# STM32_Schematics.net
KiCad netlist of a schematic drawn in Altium Designer
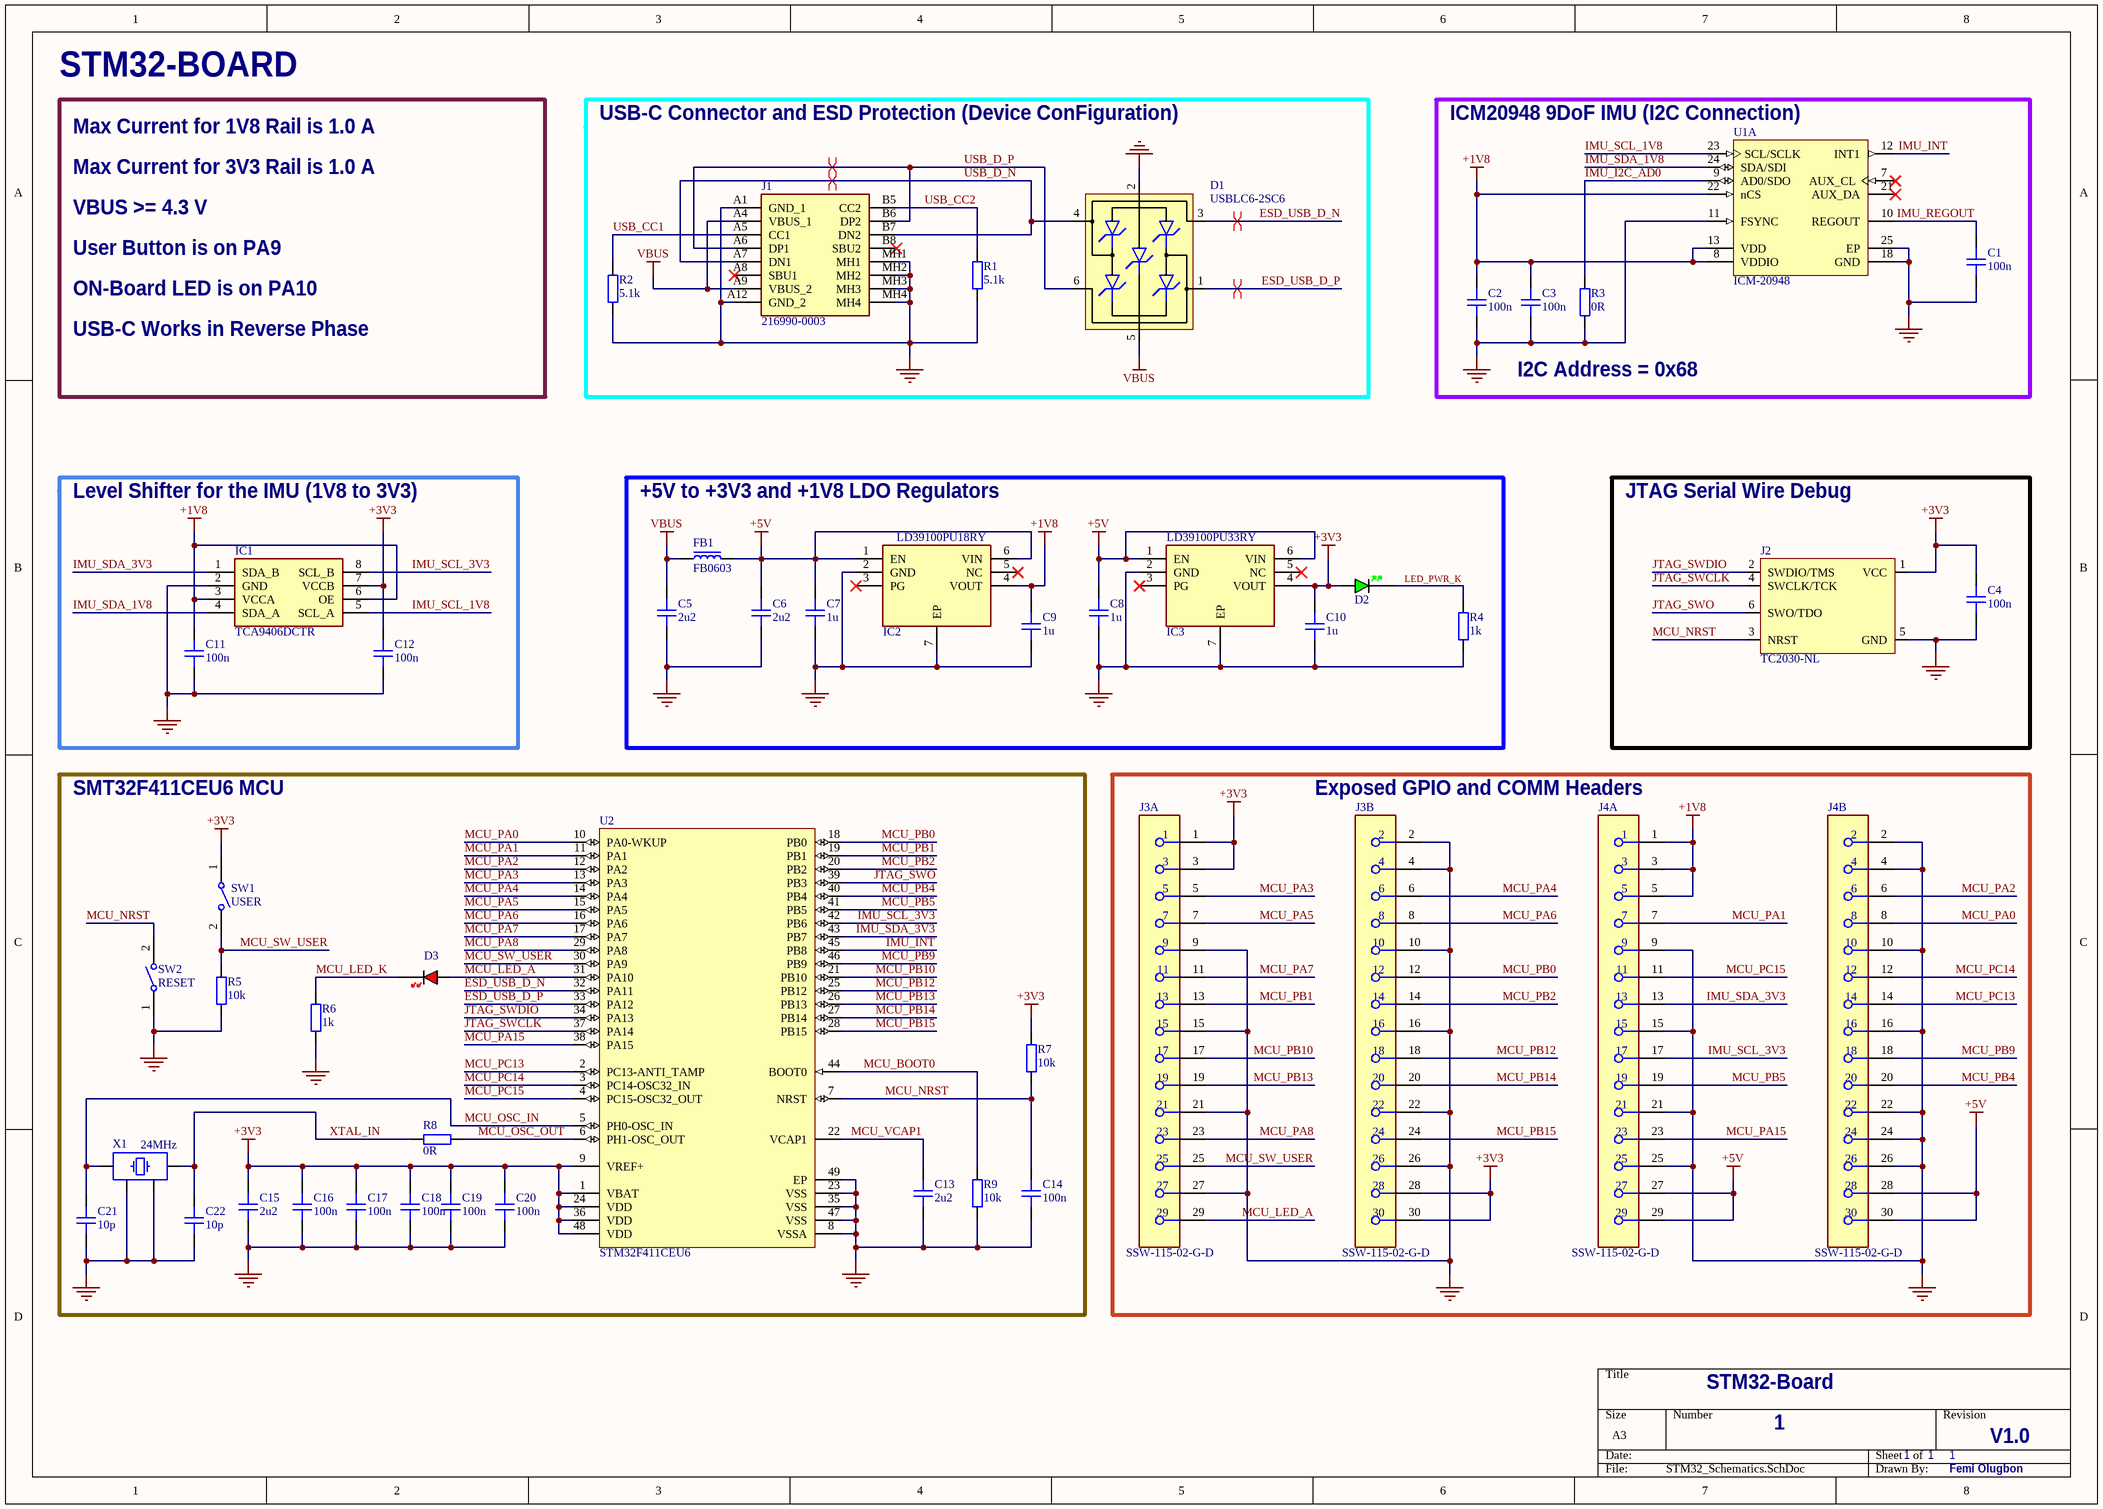
[diagram p0: STM32_Schematics.SchDoc]

(export (version "E")
  (design (tool "Eeschema 10.0.6"))
  (components
    (comp (ref "C1")
      (value "100n")
      (footprint "CAP_0402")
      (description "Capacitor SMD 0402")
      (libsource (lib "Schematic-Lib") (part "CAP_0402"))
    )
    (comp (ref "C2")
      (value "100n")
      (footprint "CAP_0402")
      (description "Capacitor SMD 0402")
      (libsource (lib "Schematic-Lib") (part "CAP_0402"))
    )
    (comp (ref "C3")
      (value "100n")
      (footprint "CAP_0402")
      (description "Capacitor SMD 0402")
      (libsource (lib "Schematic-Lib") (part "CAP_0402"))
    )
    (comp (ref "C4")
      (value "100n")
      (footprint "CAP_0402")
      (description "Capacitor SMD 0402")
      (libsource (lib "Schematic-Lib") (part "CAP_0402"))
    )
    (comp (ref "C5")
      (value "2u2")
      (footprint "CAP_0603")
      (description "Capacitor SMD 0603")
      (libsource (lib "Schematic-Lib") (part "CAP_0603"))
    )
    (comp (ref "C6")
      (value "2u2")
      (footprint "CAP_0603")
      (description "Capacitor SMD 0603")
      (libsource (lib "Schematic-Lib") (part "CAP_0603"))
    )
    (comp (ref "C7")
      (value "1u")
      (footprint "CAP_0603")
      (description "Capacitor SMD 0603")
      (libsource (lib "Schematic-Lib") (part "CAP_0603"))
    )
    (comp (ref "C8")
      (value "1u")
      (footprint "CAP_0603")
      (description "Capacitor SMD 0603")
      (libsource (lib "Schematic-Lib") (part "CAP_0603"))
    )
    (comp (ref "C9")
      (value "1u")
      (footprint "CAP_0603")
      (description "Capacitor SMD 0603")
      (libsource (lib "Schematic-Lib") (part "CAP_0603"))
    )
    (comp (ref "C10")
      (value "1u")
      (footprint "CAP_0603")
      (description "Capacitor SMD 0603")
      (libsource (lib "Schematic-Lib") (part "CAP_0603"))
    )
    (comp (ref "C11")
      (value "100n")
      (footprint "CAP_0402")
      (description "Capacitor SMD 0402")
      (libsource (lib "Schematic-Lib") (part "CAP_0402"))
    )
    (comp (ref "C12")
      (value "100n")
      (footprint "CAP_0402")
      (description "Capacitor SMD 0402")
      (libsource (lib "Schematic-Lib") (part "CAP_0402"))
    )
    (comp (ref "C13")
      (value "2u2")
      (footprint "CAP_0603")
      (description "Capacitor SMD 0603")
      (libsource (lib "Schematic-Lib") (part "CAP_0603"))
    )
    (comp (ref "C14")
      (value "100n")
      (footprint "CAP_0402")
      (description "Capacitor SMD 0402")
      (libsource (lib "Schematic-Lib") (part "CAP_0402"))
    )
    (comp (ref "C15")
      (value "2u2")
      (footprint "CAP_0603")
      (description "Capacitor SMD 0603")
      (libsource (lib "Schematic-Lib") (part "CAP_0603"))
    )
    (comp (ref "C16")
      (value "100n")
      (footprint "CAP_0402")
      (description "Capacitor SMD 0402")
      (libsource (lib "Schematic-Lib") (part "CAP_0402"))
    )
    (comp (ref "C17")
      (value "100n")
      (footprint "CAP_0402")
      (description "Capacitor SMD 0402")
      (libsource (lib "Schematic-Lib") (part "CAP_0402"))
    )
    (comp (ref "C18")
      (value "100n")
      (footprint "CAP_0402")
      (description "Capacitor SMD 0402")
      (libsource (lib "Schematic-Lib") (part "CAP_0402"))
    )
    (comp (ref "C19")
      (value "100n")
      (footprint "CAP_0402")
      (description "Capacitor SMD 0402")
      (libsource (lib "Schematic-Lib") (part "CAP_0402"))
    )
    (comp (ref "C20")
      (value "100n")
      (footprint "CAP_0402")
      (description "Capacitor SMD 0402")
      (libsource (lib "Schematic-Lib") (part "CAP_0402"))
    )
    (comp (ref "C21")
      (value "10p")
      (footprint "CAP_0402")
      (description "Capacitor SMD 0402")
      (libsource (lib "Schematic-Lib") (part "CAP_0402"))
    )
    (comp (ref "C22")
      (value "10p")
      (footprint "CAP_0402")
      (description "Capacitor SMD 0402")
      (libsource (lib "Schematic-Lib") (part "CAP_0402"))
    )
    (comp (ref "D1")
      (value "USBLC6-2SC6")
      (footprint "SOT-23-6")
      (description "Low-Capacitance ESD Protection USB")
      (fields (field (name "MANUFACTURER") "STMicroelectronics"))
      (libsource (lib "Schematic-Lib") (part "USBLC6-2SC6"))
    )
    (comp (ref "D2")
      (value "GREEN")
      (footprint "LED_0402_GREEN")
      (description "LED 0402 GREEN SMD")
      (libsource (lib "Schematic-Lib") (part "LED_0402_GREEN"))
    )
    (comp (ref "D3")
      (value "RED")
      (footprint "LED_0402_RED")
      (description "LED 0402 RED SMD")
      (libsource (lib "Schematic-Lib") (part "LED_0402_RED"))
    )
    (comp (ref "FB1")
      (value "FB0603")
      (footprint "FB_0603")
      (description "Ferrite Bead SMD 0603")
      (libsource (lib "Schematic-Lib") (part "FB_0603"))
    )
    (comp (ref "IC1")
      (value "TCA9406DCTR")
      (footprint "SamacSys:SOP65P400X130-8N")
      (description "Integrated Circuit")
      (fields (field (name "MOUSER PART NUMBER") "595-TCA9406DCTR"))
      (libsource (lib "*") (part "TCA9406DCTR"))
    )
    (comp (ref "IC2")
      (value "LD39100PU18RY")
      (footprint "SamacSys:SON95P300X300X90-7N-D")
      (description "Integrated Circuit")
      (fields (field (name "MOUSER PART NUMBER") "511-LD39100PU18RY"))
      (libsource (lib "Schematic-Lib") (part "LD39100PU18RY"))
    )
    (comp (ref "IC3")
      (value "LD39100PU33RY")
      (footprint "SamacSys:SON95P300X300X90-7N-D")
      (description "Integrated Circuit")
      (fields (field (name "MOUSER PART NUMBER") "511-LD39100PU33RY"))
      (libsource (lib "Schematic-Lib") (part "LD39100PU33RY"))
    )
    (comp (ref "J1")
      (value "216990-0003")
      (footprint "2169900003")
      (description "Connector")
      (fields (field (name "MOUSER PART NUMBER") "538-216990-0003"))
      (libsource (lib "Schematic-Lib") (part "216990-0003"))
    )
    (comp (ref "J2")
      (value "TC2030-NL")
      (footprint "TC2030-NL-FP")
      (description "Tag-Connect No-Solder SWD Debug Connector (No Legs) DO NOT PLACE")
      (fields
        (field (name "MANUFACTURER") "Tag-Connect")
        (field (name "MANUFACTURER PART NUMBER") "TC2030-NL-FP")
      )
      (libsource (lib "Schematic-Lib") (part "TC2030-NL"))
    )
    (comp (ref "J3")
      (value "SSW-115-02-G-D")
      (footprint "FP-SSW-115-02-G-D-MFG")
      (description "SSW-115-02-G-D SSW - Samtec 2.54mm Dual Row Straight Socket Strip 8.5mm Profile (mcv)(TO22)")
      (libsource (lib "Altium Content Vault") (part "58658856964e77fd1e9d81751433862"))
    )
    (comp (ref "J4")
      (value "SSW-115-02-G-D")
      (footprint "FP-SSW-115-02-G-D-MFG")
      (description "SSW-115-02-G-D SSW - Samtec 2.54mm Dual Row Straight Socket Strip 8.5mm Profile (mcv)(TO22)")
      (libsource (lib "Altium Content Vault") (part "58658856964e77fd1e9d81751433862"))
    )
    (comp (ref "R1")
      (value "5.1k")
      (footprint "RES_0402")
      (description "Resistor SMD 0402")
      (libsource (lib "Schematic-Lib") (part "RES_0402"))
    )
    (comp (ref "R2")
      (value "5.1k")
      (footprint "RES_0402")
      (description "Resistor SMD 0402")
      (libsource (lib "Schematic-Lib") (part "RES_0402"))
    )
    (comp (ref "R3")
      (value "0R")
      (footprint "RES_0402")
      (description "Resistor SMD 0402")
      (libsource (lib "Schematic-Lib") (part "RES_0402"))
    )
    (comp (ref "R4")
      (value "1k")
      (footprint "RES_0402")
      (description "Resistor SMD 0402")
      (libsource (lib "Schematic-Lib") (part "RES_0402"))
    )
    (comp (ref "R5")
      (value "10k")
      (footprint "RES_0402")
      (description "Resistor SMD 0402")
      (libsource (lib "Schematic-Lib") (part "RES_0402"))
    )
    (comp (ref "R6")
      (value "1k")
      (footprint "RES_0402")
      (description "Resistor SMD 0402")
      (libsource (lib "Schematic-Lib") (part "RES_0402"))
    )
    (comp (ref "R7")
      (value "10k")
      (footprint "RES_0402")
      (description "Resistor SMD 0402")
      (libsource (lib "Schematic-Lib") (part "RES_0402"))
    )
    (comp (ref "R8")
      (value "0R")
      (footprint "RES_0402")
      (description "Resistor SMD 0402")
      (libsource (lib "Schematic-Lib") (part "RES_0402"))
    )
    (comp (ref "R9")
      (value "10k")
      (footprint "RES_0402")
      (description "Resistor SMD 0402")
      (libsource (lib "Schematic-Lib") (part "RES_0402"))
    )
    (comp (ref "SW1")
      (value "USER")
      (footprint "TECO-FSMSM-2_V")
      (description "FSMSM Push Button Switch, 50 mA, -35 to 85 degC, 2-Pin SMD, RoHS, Bulk")
      (fields (field (name "MANUFACTURER") "TE Connectivity"))
      (libsource (lib "Altium Content Vault") (part "SW-SPST-2_C"))
    )
    (comp (ref "SW2")
      (value "RESET")
      (footprint "TECO-FSMSM-2_V")
      (description "FSMSM Push Button Switch, 50 mA, -35 to 85 degC, 2-Pin SMD, RoHS, Bulk")
      (fields (field (name "MANUFACTURER") "TE Connectivity"))
      (libsource (lib "Altium Content Vault") (part "SW-SPST-2_C"))
    )
    (comp (ref "U1")
      (value "ICM-20948")
      (footprint "TDK-QFN-24_L")
      (fields (field (name "MANUFACTURER") "TDK"))
      (libsource (lib "Altium Content Vault") (part "TDK-ICM-20948-QFN-24"))
    )
    (comp (ref "U2")
      (value "STM32F411CEU6")
      (footprint "STM-UFQFPN48_L")
      (libsource (lib "Altium Content Vault") (part "MC-ARM-STM32F411-UFQFPN48"))
    )
    (comp (ref "X1")
      (value "24MHz")
      (footprint "XTAL_3225")
      (description "Crystal SMD 24MHz 10PPM 7pF 3225")
      (fields
        (field (name "MANUFACTURER") "Epson")
        (field (name "MANUFACTURER PART NUMBER") "TSX-3225 24.0000MF15X-AC")
      )
      (libsource (lib "Schematic-Lib") (part "TSX-3225_24.0000MF15X-AC"))
    )
  )
  (nets
    (net (code "1") (name "+1V8") (class "Default")
      (node (ref "C11") (pin "1") (pinfunction "1_1") (pintype "passive"))
      (node (ref "C2") (pin "1") (pinfunction "1_1") (pintype "passive"))
      (node (ref "C3") (pin "1") (pinfunction "1_1") (pintype "passive"))
      (node (ref "C9") (pin "2") (pinfunction "2_2") (pintype "passive"))
      (node (ref "IC1") (pin "3") (pinfunction "VCCA_3") (pintype "passive"))
      (node (ref "IC1") (pin "6") (pinfunction "OE_6") (pintype "passive"))
      (node (ref "IC2") (pin "4") (pinfunction "VOUT_4") (pintype "passive"))
      (node (ref "J4") (pin "1") (pinfunction "1_1") (pintype "passive"))
      (node (ref "J4") (pin "3") (pinfunction "3_3") (pintype "passive"))
      (node (ref "J4") (pin "5") (pinfunction "5_5") (pintype "passive"))
      (node (ref "U1") (pin "13") (pinfunction "VDD_13") (pintype "power_in"))
      (node (ref "U1") (pin "22") (pinfunction "nCS_22") (pintype "input"))
      (node (ref "U1") (pin "8") (pinfunction "VDDIO_8") (pintype "power_in"))
    )
    (net (code "2") (name "+3V3") (class "Default")
      (node (ref "C10") (pin "2") (pinfunction "2_2") (pintype "passive"))
      (node (ref "C12") (pin "1") (pinfunction "1_1") (pintype "passive"))
      (node (ref "C15") (pin "2") (pinfunction "2_2") (pintype "passive"))
      (node (ref "C16") (pin "1") (pinfunction "1_1") (pintype "passive"))
      (node (ref "C17") (pin "1") (pinfunction "1_1") (pintype "passive"))
      (node (ref "C18") (pin "1") (pinfunction "1_1") (pintype "passive"))
      (node (ref "C19") (pin "1") (pinfunction "1_1") (pintype "passive"))
      (node (ref "C20") (pin "1") (pinfunction "1_1") (pintype "passive"))
      (node (ref "C4") (pin "1") (pinfunction "1_1") (pintype "passive"))
      (node (ref "D2") (pin "A") (pinfunction "A_A") (pintype "passive"))
      (node (ref "IC1") (pin "7") (pinfunction "VCCB_7") (pintype "passive"))
      (node (ref "IC3") (pin "4") (pinfunction "VOUT_4") (pintype "passive"))
      (node (ref "J2") (pin "1") (pinfunction "VCC_1") (pintype "passive"))
      (node (ref "J3") (pin "1") (pinfunction "1_1") (pintype "passive"))
      (node (ref "J3") (pin "28") (pinfunction "28_28") (pintype "passive"))
      (node (ref "J3") (pin "3") (pinfunction "3_3") (pintype "passive"))
      (node (ref "J3") (pin "30") (pinfunction "30_30") (pintype "passive"))
      (node (ref "R7") (pin "2") (pinfunction "2_2") (pintype "passive"))
      (node (ref "SW1") (pin "1") (pinfunction "1_1") (pintype "passive"))
      (node (ref "U2") (pin "1") (pinfunction "VBAT_1") (pintype "power_in"))
      (node (ref "U2") (pin "24") (pinfunction "VDD_24") (pintype "power_in"))
      (node (ref "U2") (pin "36") (pinfunction "VDD_36") (pintype "power_in"))
      (node (ref "U2") (pin "48") (pinfunction "VDD_48") (pintype "power_in"))
      (node (ref "U2") (pin "9") (pinfunction "VREF+_9") (pintype "power_in"))
    )
    (net (code "3") (name "+5V") (class "Default")
      (node (ref "C6") (pin "2") (pinfunction "2_2") (pintype "passive"))
      (node (ref "C7") (pin "2") (pinfunction "2_2") (pintype "passive"))
      (node (ref "C8") (pin "2") (pinfunction "2_2") (pintype "passive"))
      (node (ref "FB1") (pin "2") (pinfunction "2_2") (pintype "passive"))
      (node (ref "IC2") (pin "1") (pinfunction "EN_1") (pintype "passive"))
      (node (ref "IC2") (pin "6") (pinfunction "VIN_6") (pintype "passive"))
      (node (ref "IC3") (pin "1") (pinfunction "EN_1") (pintype "passive"))
      (node (ref "IC3") (pin "6") (pinfunction "VIN_6") (pintype "passive"))
      (node (ref "J4") (pin "27") (pinfunction "27_27") (pintype "passive"))
      (node (ref "J4") (pin "28") (pinfunction "28_28") (pintype "passive"))
      (node (ref "J4") (pin "29") (pinfunction "29_29") (pintype "passive"))
      (node (ref "J4") (pin "30") (pinfunction "30_30") (pintype "passive"))
    )
    (net (code "4") (name "/ESD_USB_D_N") (class "Default")
      (node (ref "D1") (pin "3") (pinfunction "IO2_3") (pintype "bidirectional"))
      (node (ref "U2") (pin "32") (pinfunction "PA11_32") (pintype "bidirectional"))
    )
    (net (code "5") (name "/ESD_USB_D_P") (class "Default")
      (node (ref "D1") (pin "1") (pinfunction "IO1_1") (pintype "bidirectional"))
      (node (ref "U2") (pin "33") (pinfunction "PA12_33") (pintype "bidirectional"))
    )
    (net (code "6") (name "/IMU_I2C_AD0") (class "Default")
      (node (ref "R3") (pin "2") (pinfunction "2_2") (pintype "passive"))
      (node (ref "U1") (pin "9") (pinfunction "AD0/SDO_9") (pintype "bidirectional"))
    )
    (net (code "7") (name "/IMU_INT") (class "Default")
      (node (ref "U1") (pin "12") (pinfunction "INT1_12") (pintype "output"))
      (node (ref "U2") (pin "45") (pinfunction "PB8_45") (pintype "bidirectional"))
    )
    (net (code "8") (name "/IMU_REGOUT") (class "Default")
      (node (ref "C1") (pin "1") (pinfunction "1_1") (pintype "passive"))
      (node (ref "U1") (pin "10") (pinfunction "REGOUT_10") (pintype "passive"))
    )
    (net (code "9") (name "/IMU_SCL_1V8") (class "Default")
      (node (ref "IC1") (pin "5") (pinfunction "SCL_A_5") (pintype "passive"))
      (node (ref "U1") (pin "23") (pinfunction "SCL/SCLK_23") (pintype "input"))
    )
    (net (code "10") (name "/IMU_SCL_3V3") (class "Default")
      (node (ref "IC1") (pin "8") (pinfunction "SCL_B_8") (pintype "passive"))
      (node (ref "J4") (pin "17") (pinfunction "17_17") (pintype "passive"))
      (node (ref "U2") (pin "42") (pinfunction "PB6_42") (pintype "bidirectional"))
    )
    (net (code "11") (name "/IMU_SDA_1V8") (class "Default")
      (node (ref "IC1") (pin "4") (pinfunction "SDA_A_4") (pintype "passive"))
      (node (ref "U1") (pin "24") (pinfunction "SDA/SDI_24") (pintype "bidirectional"))
    )
    (net (code "12") (name "/IMU_SDA_3V3") (class "Default")
      (node (ref "IC1") (pin "1") (pinfunction "SDA_B_1") (pintype "passive"))
      (node (ref "J4") (pin "13") (pinfunction "13_13") (pintype "passive"))
      (node (ref "U2") (pin "43") (pinfunction "PB7_43") (pintype "bidirectional"))
    )
    (net (code "13") (name "/JTAG_SWCLK") (class "Default")
      (node (ref "J2") (pin "4") (pinfunction "SWCLK/TCK_4") (pintype "passive"))
      (node (ref "U2") (pin "37") (pinfunction "PA14_37") (pintype "bidirectional"))
    )
    (net (code "14") (name "/JTAG_SWDIO") (class "Default")
      (node (ref "J2") (pin "2") (pinfunction "SWDIO/TMS_2") (pintype "passive"))
      (node (ref "U2") (pin "34") (pinfunction "PA13_34") (pintype "bidirectional"))
    )
    (net (code "15") (name "/JTAG_SWO") (class "Default")
      (node (ref "J2") (pin "6") (pinfunction "SWO/TDO_6") (pintype "passive"))
      (node (ref "U2") (pin "39") (pinfunction "PB3_39") (pintype "bidirectional"))
    )
    (net (code "16") (name "/LED_PWR_K") (class "Default")
      (node (ref "D2") (pin "K") (pinfunction "K_K") (pintype "passive"))
      (node (ref "R4") (pin "2") (pinfunction "2_2") (pintype "passive"))
    )
    (net (code "17") (name "/MCU_BOOT0") (class "Default")
      (node (ref "R9") (pin "2") (pinfunction "2_2") (pintype "passive"))
      (node (ref "U2") (pin "44") (pinfunction "BOOT0_44") (pintype "input"))
    )
    (net (code "18") (name "/MCU_LED_A") (class "Default")
      (node (ref "D3") (pin "A") (pinfunction "A_A") (pintype "passive"))
      (node (ref "J3") (pin "29") (pinfunction "29_29") (pintype "passive"))
      (node (ref "U2") (pin "31") (pinfunction "PA10_31") (pintype "bidirectional"))
    )
    (net (code "19") (name "/MCU_LED_K") (class "Default")
      (node (ref "D3") (pin "K") (pinfunction "K_K") (pintype "passive"))
      (node (ref "R6") (pin "1") (pinfunction "1_1") (pintype "passive"))
    )
    (net (code "20") (name "/MCU_NRST") (class "Default")
      (node (ref "C14") (pin "1") (pinfunction "1_1") (pintype "passive"))
      (node (ref "J2") (pin "3") (pinfunction "NRST_3") (pintype "passive"))
      (node (ref "R7") (pin "1") (pinfunction "1_1") (pintype "passive"))
      (node (ref "SW2") (pin "2") (pinfunction "2_2") (pintype "passive"))
      (node (ref "U2") (pin "7") (pinfunction "NRST_7") (pintype "bidirectional"))
    )
    (net (code "21") (name "/MCU_OSC_IN") (class "Default")
      (node (ref "C21") (pin "1") (pinfunction "1_1") (pintype "passive"))
      (node (ref "U2") (pin "5") (pinfunction "PH0-OSC_IN_5") (pintype "bidirectional"))
      (node (ref "X1") (pin "1") (pinfunction "1_1") (pintype "passive"))
    )
    (net (code "22") (name "/MCU_OSC_OUT") (class "Default")
      (node (ref "R8") (pin "1") (pinfunction "1_1") (pintype "passive"))
      (node (ref "U2") (pin "6") (pinfunction "PH1-OSC_OUT_6") (pintype "bidirectional"))
    )
    (net (code "23") (name "/MCU_PA0") (class "Default")
      (node (ref "J4") (pin "8") (pinfunction "8_8") (pintype "passive"))
      (node (ref "U2") (pin "10") (pinfunction "PA0-WKUP_10") (pintype "bidirectional"))
    )
    (net (code "24") (name "/MCU_PA1") (class "Default")
      (node (ref "J4") (pin "7") (pinfunction "7_7") (pintype "passive"))
      (node (ref "U2") (pin "11") (pinfunction "PA1_11") (pintype "bidirectional"))
    )
    (net (code "25") (name "/MCU_PA2") (class "Default")
      (node (ref "J4") (pin "6") (pinfunction "6_6") (pintype "passive"))
      (node (ref "U2") (pin "12") (pinfunction "PA2_12") (pintype "bidirectional"))
    )
    (net (code "26") (name "/MCU_PA3") (class "Default")
      (node (ref "J3") (pin "5") (pinfunction "5_5") (pintype "passive"))
      (node (ref "U2") (pin "13") (pinfunction "PA3_13") (pintype "bidirectional"))
    )
    (net (code "27") (name "/MCU_PA4") (class "Default")
      (node (ref "J3") (pin "6") (pinfunction "6_6") (pintype "passive"))
      (node (ref "U2") (pin "14") (pinfunction "PA4_14") (pintype "bidirectional"))
    )
    (net (code "28") (name "/MCU_PA5") (class "Default")
      (node (ref "J3") (pin "7") (pinfunction "7_7") (pintype "passive"))
      (node (ref "U2") (pin "15") (pinfunction "PA5_15") (pintype "bidirectional"))
    )
    (net (code "29") (name "/MCU_PA6") (class "Default")
      (node (ref "J3") (pin "8") (pinfunction "8_8") (pintype "passive"))
      (node (ref "U2") (pin "16") (pinfunction "PA6_16") (pintype "bidirectional"))
    )
    (net (code "30") (name "/MCU_PA7") (class "Default")
      (node (ref "J3") (pin "11") (pinfunction "11_11") (pintype "passive"))
      (node (ref "U2") (pin "17") (pinfunction "PA7_17") (pintype "bidirectional"))
    )
    (net (code "31") (name "/MCU_PA8") (class "Default")
      (node (ref "J3") (pin "23") (pinfunction "23_23") (pintype "passive"))
      (node (ref "U2") (pin "29") (pinfunction "PA8_29") (pintype "bidirectional"))
    )
    (net (code "32") (name "/MCU_PA15") (class "Default")
      (node (ref "J4") (pin "23") (pinfunction "23_23") (pintype "passive"))
      (node (ref "U2") (pin "38") (pinfunction "PA15_38") (pintype "bidirectional"))
    )
    (net (code "33") (name "/MCU_PB0") (class "Default")
      (node (ref "J3") (pin "12") (pinfunction "12_12") (pintype "passive"))
      (node (ref "U2") (pin "18") (pinfunction "PB0_18") (pintype "bidirectional"))
    )
    (net (code "34") (name "/MCU_PB1") (class "Default")
      (node (ref "J3") (pin "13") (pinfunction "13_13") (pintype "passive"))
      (node (ref "U2") (pin "19") (pinfunction "PB1_19") (pintype "bidirectional"))
    )
    (net (code "35") (name "/MCU_PB2") (class "Default")
      (node (ref "J3") (pin "14") (pinfunction "14_14") (pintype "passive"))
      (node (ref "U2") (pin "20") (pinfunction "PB2_20") (pintype "bidirectional"))
    )
    (net (code "36") (name "/MCU_PB4") (class "Default")
      (node (ref "J4") (pin "20") (pinfunction "20_20") (pintype "passive"))
      (node (ref "U2") (pin "40") (pinfunction "PB4_40") (pintype "bidirectional"))
    )
    (net (code "37") (name "/MCU_PB5") (class "Default")
      (node (ref "J4") (pin "19") (pinfunction "19_19") (pintype "passive"))
      (node (ref "U2") (pin "41") (pinfunction "PB5_41") (pintype "bidirectional"))
    )
    (net (code "38") (name "/MCU_PB9") (class "Default")
      (node (ref "J4") (pin "18") (pinfunction "18_18") (pintype "passive"))
      (node (ref "U2") (pin "46") (pinfunction "PB9_46") (pintype "bidirectional"))
    )
    (net (code "39") (name "/MCU_PB10") (class "Default")
      (node (ref "J3") (pin "17") (pinfunction "17_17") (pintype "passive"))
      (node (ref "U2") (pin "21") (pinfunction "PB10_21") (pintype "bidirectional"))
    )
    (net (code "40") (name "/MCU_PB12") (class "Default")
      (node (ref "J3") (pin "18") (pinfunction "18_18") (pintype "passive"))
      (node (ref "U2") (pin "25") (pinfunction "PB12_25") (pintype "bidirectional"))
    )
    (net (code "41") (name "/MCU_PB13") (class "Default")
      (node (ref "J3") (pin "19") (pinfunction "19_19") (pintype "passive"))
      (node (ref "U2") (pin "26") (pinfunction "PB13_26") (pintype "bidirectional"))
    )
    (net (code "42") (name "/MCU_PB14") (class "Default")
      (node (ref "J3") (pin "20") (pinfunction "20_20") (pintype "passive"))
      (node (ref "U2") (pin "27") (pinfunction "PB14_27") (pintype "bidirectional"))
    )
    (net (code "43") (name "/MCU_PB15") (class "Default")
      (node (ref "J3") (pin "24") (pinfunction "24_24") (pintype "passive"))
      (node (ref "U2") (pin "28") (pinfunction "PB15_28") (pintype "bidirectional"))
    )
    (net (code "44") (name "/MCU_PC13") (class "Default")
      (node (ref "J4") (pin "14") (pinfunction "14_14") (pintype "passive"))
      (node (ref "U2") (pin "2") (pinfunction "PC13-ANTI_TAMP_2") (pintype "bidirectional"))
    )
    (net (code "45") (name "/MCU_PC14") (class "Default")
      (node (ref "J4") (pin "12") (pinfunction "12_12") (pintype "passive"))
      (node (ref "U2") (pin "3") (pinfunction "PC14-OSC32_IN_3") (pintype "bidirectional"))
    )
    (net (code "46") (name "/MCU_PC15") (class "Default")
      (node (ref "J4") (pin "11") (pinfunction "11_11") (pintype "passive"))
      (node (ref "U2") (pin "4") (pinfunction "PC15-OSC32_OUT_4") (pintype "bidirectional"))
    )
    (net (code "47") (name "/MCU_SW_USER") (class "Default")
      (node (ref "J3") (pin "25") (pinfunction "25_25") (pintype "passive"))
      (node (ref "R5") (pin "2") (pinfunction "2_2") (pintype "passive"))
      (node (ref "SW1") (pin "2") (pinfunction "2_2") (pintype "passive"))
      (node (ref "U2") (pin "30") (pinfunction "PA9_30") (pintype "bidirectional"))
    )
    (net (code "48") (name "/MCU_VCAP1") (class "Default")
      (node (ref "C13") (pin "2") (pinfunction "2_2") (pintype "passive"))
      (node (ref "U2") (pin "22") (pinfunction "VCAP1_22") (pintype "passive"))
    )
    (net (code "49") (name "/USB_CC1") (class "Default")
      (node (ref "J1") (pin "A5") (pinfunction "CC1_A5") (pintype "passive"))
      (node (ref "R2") (pin "2") (pinfunction "2_2") (pintype "passive"))
    )
    (net (code "50") (name "/USB_CC2") (class "Default")
      (node (ref "J1") (pin "B5") (pinfunction "CC2_B5") (pintype "passive"))
      (node (ref "R1") (pin "2") (pinfunction "2_2") (pintype "passive"))
    )
    (net (code "51") (name "/USB_D_N") (class "Default")
      (node (ref "D1") (pin "4") (pinfunction "IO2_4") (pintype "bidirectional"))
      (node (ref "J1") (pin "A7") (pinfunction "DN1_A7") (pintype "passive"))
      (node (ref "J1") (pin "B7") (pinfunction "DN2_B7") (pintype "passive"))
    )
    (net (code "52") (name "/USB_D_P") (class "Default")
      (node (ref "D1") (pin "6") (pinfunction "IO1_6") (pintype "bidirectional"))
      (node (ref "J1") (pin "A6") (pinfunction "DP1_A6") (pintype "passive"))
      (node (ref "J1") (pin "B6") (pinfunction "DP2_B6") (pintype "passive"))
    )
    (net (code "53") (name "/XTAL_IN") (class "Default")
      (node (ref "C22") (pin "1") (pinfunction "1_1") (pintype "passive"))
      (node (ref "R8") (pin "2") (pinfunction "2_2") (pintype "passive"))
      (node (ref "X1") (pin "3") (pinfunction "3_3") (pintype "passive"))
    )
    (net (code "54") (name "GND") (class "Default")
      (node (ref "C1") (pin "2") (pinfunction "2_2") (pintype "passive"))
      (node (ref "C10") (pin "1") (pinfunction "1_1") (pintype "passive"))
      (node (ref "C11") (pin "2") (pinfunction "2_2") (pintype "passive"))
      (node (ref "C12") (pin "2") (pinfunction "2_2") (pintype "passive"))
      (node (ref "C13") (pin "1") (pinfunction "1_1") (pintype "passive"))
      (node (ref "C14") (pin "2") (pinfunction "2_2") (pintype "passive"))
      (node (ref "C15") (pin "1") (pinfunction "1_1") (pintype "passive"))
      (node (ref "C16") (pin "2") (pinfunction "2_2") (pintype "passive"))
      (node (ref "C17") (pin "2") (pinfunction "2_2") (pintype "passive"))
      (node (ref "C18") (pin "2") (pinfunction "2_2") (pintype "passive"))
      (node (ref "C19") (pin "2") (pinfunction "2_2") (pintype "passive"))
      (node (ref "C2") (pin "2") (pinfunction "2_2") (pintype "passive"))
      (node (ref "C20") (pin "2") (pinfunction "2_2") (pintype "passive"))
      (node (ref "C21") (pin "2") (pinfunction "2_2") (pintype "passive"))
      (node (ref "C22") (pin "2") (pinfunction "2_2") (pintype "passive"))
      (node (ref "C3") (pin "2") (pinfunction "2_2") (pintype "passive"))
      (node (ref "C4") (pin "2") (pinfunction "2_2") (pintype "passive"))
      (node (ref "C5") (pin "1") (pinfunction "1_1") (pintype "passive"))
      (node (ref "C6") (pin "1") (pinfunction "1_1") (pintype "passive"))
      (node (ref "C7") (pin "1") (pinfunction "1_1") (pintype "passive"))
      (node (ref "C8") (pin "1") (pinfunction "1_1") (pintype "passive"))
      (node (ref "C9") (pin "1") (pinfunction "1_1") (pintype "passive"))
      (node (ref "D1") (pin "2") (pinfunction "GND_2") (pintype "power_in"))
      (node (ref "IC1") (pin "2") (pinfunction "GND_2") (pintype "passive"))
      (node (ref "IC2") (pin "2") (pinfunction "GND_2") (pintype "passive"))
      (node (ref "IC2") (pin "7") (pinfunction "EP_7") (pintype "passive"))
      (node (ref "IC3") (pin "2") (pinfunction "GND_2") (pintype "passive"))
      (node (ref "IC3") (pin "7") (pinfunction "EP_7") (pintype "passive"))
      (node (ref "J1") (pin "A1") (pinfunction "GND_1_A1") (pintype "passive"))
      (node (ref "J1") (pin "A12") (pinfunction "GND_2_A12") (pintype "passive"))
      (node (ref "J1") (pin "MH1") (pinfunction "MH1_MH1") (pintype "passive"))
      (node (ref "J1") (pin "MH2") (pinfunction "MH2_MH2") (pintype "passive"))
      (node (ref "J1") (pin "MH3") (pinfunction "MH3_MH3") (pintype "passive"))
      (node (ref "J1") (pin "MH4") (pinfunction "MH4_MH4") (pintype "passive"))
      (node (ref "J2") (pin "5") (pinfunction "GND_5") (pintype "passive"))
      (node (ref "J3") (pin "10") (pinfunction "10_10") (pintype "passive"))
      (node (ref "J3") (pin "15") (pinfunction "15_15") (pintype "passive"))
      (node (ref "J3") (pin "16") (pinfunction "16_16") (pintype "passive"))
      (node (ref "J3") (pin "2") (pinfunction "2_2") (pintype "passive"))
      (node (ref "J3") (pin "21") (pinfunction "21_21") (pintype "passive"))
      (node (ref "J3") (pin "22") (pinfunction "22_22") (pintype "passive"))
      (node (ref "J3") (pin "26") (pinfunction "26_26") (pintype "passive"))
      (node (ref "J3") (pin "27") (pinfunction "27_27") (pintype "passive"))
      (node (ref "J3") (pin "4") (pinfunction "4_4") (pintype "passive"))
      (node (ref "J3") (pin "9") (pinfunction "9_9") (pintype "passive"))
      (node (ref "J4") (pin "10") (pinfunction "10_10") (pintype "passive"))
      (node (ref "J4") (pin "15") (pinfunction "15_15") (pintype "passive"))
      (node (ref "J4") (pin "16") (pinfunction "16_16") (pintype "passive"))
      (node (ref "J4") (pin "2") (pinfunction "2_2") (pintype "passive"))
      (node (ref "J4") (pin "21") (pinfunction "21_21") (pintype "passive"))
      (node (ref "J4") (pin "22") (pinfunction "22_22") (pintype "passive"))
      (node (ref "J4") (pin "24") (pinfunction "24_24") (pintype "passive"))
      (node (ref "J4") (pin "25") (pinfunction "25_25") (pintype "passive"))
      (node (ref "J4") (pin "26") (pinfunction "26_26") (pintype "passive"))
      (node (ref "J4") (pin "4") (pinfunction "4_4") (pintype "passive"))
      (node (ref "J4") (pin "9") (pinfunction "9_9") (pintype "passive"))
      (node (ref "R1") (pin "1") (pinfunction "1_1") (pintype "passive"))
      (node (ref "R2") (pin "1") (pinfunction "1_1") (pintype "passive"))
      (node (ref "R3") (pin "1") (pinfunction "1_1") (pintype "passive"))
      (node (ref "R4") (pin "1") (pinfunction "1_1") (pintype "passive"))
      (node (ref "R5") (pin "1") (pinfunction "1_1") (pintype "passive"))
      (node (ref "R6") (pin "2") (pinfunction "2_2") (pintype "passive"))
      (node (ref "R9") (pin "1") (pinfunction "1_1") (pintype "passive"))
      (node (ref "SW2") (pin "1") (pinfunction "1_1") (pintype "passive"))
      (node (ref "U1") (pin "11") (pinfunction "FSYNC_11") (pintype "input"))
      (node (ref "U1") (pin "18") (pinfunction "GND_18") (pintype "power_in"))
      (node (ref "U1") (pin "25") (pinfunction "EP_25") (pintype "passive"))
      (node (ref "U2") (pin "23") (pinfunction "VSS_23") (pintype "power_in"))
      (node (ref "U2") (pin "35") (pinfunction "VSS_35") (pintype "power_in"))
      (node (ref "U2") (pin "47") (pinfunction "VSS_47") (pintype "power_in"))
      (node (ref "U2") (pin "49") (pinfunction "EP_49") (pintype "power_in"))
      (node (ref "U2") (pin "8") (pinfunction "VSSA_8") (pintype "power_in"))
      (node (ref "X1") (pin "2") (pinfunction "2_2") (pintype "passive"))
      (node (ref "X1") (pin "4") (pinfunction "4_4") (pintype "passive"))
    )
    (net (code "55") (name "VBUS") (class "Default")
      (node (ref "C5") (pin "2") (pinfunction "2_2") (pintype "passive"))
      (node (ref "D1") (pin "5") (pinfunction "VBUS_5") (pintype "power_in"))
      (node (ref "FB1") (pin "1") (pinfunction "1_1") (pintype "passive"))
      (node (ref "J1") (pin "A4") (pinfunction "VBUS_1_A4") (pintype "passive"))
      (node (ref "J1") (pin "A9") (pinfunction "VBUS_2_A9") (pintype "passive"))
    )
    (net (code "56") (name "unconnected-(IC2-NC-Pad5)") (class "Default")
      (node (ref "IC2") (pin "5") (pinfunction "NC_5") (pintype "passive+no_connect"))
    )
    (net (code "57") (name "unconnected-(IC2-PG-Pad3)") (class "Default")
      (node (ref "IC2") (pin "3") (pinfunction "PG_3") (pintype "passive+no_connect"))
    )
    (net (code "58") (name "unconnected-(IC3-NC-Pad5)") (class "Default")
      (node (ref "IC3") (pin "5") (pinfunction "NC_5") (pintype "passive+no_connect"))
    )
    (net (code "59") (name "unconnected-(IC3-PG-Pad3)") (class "Default")
      (node (ref "IC3") (pin "3") (pinfunction "PG_3") (pintype "passive+no_connect"))
    )
    (net (code "60") (name "unconnected-(J1-SBU1-PadA8)") (class "Default")
      (node (ref "J1") (pin "A8") (pinfunction "SBU1_A8") (pintype "passive+no_connect"))
    )
    (net (code "61") (name "unconnected-(J1-SBU2-PadB8)") (class "Default")
      (node (ref "J1") (pin "B8") (pinfunction "SBU2_B8") (pintype "passive+no_connect"))
    )
    (net (code "62") (name "unconnected-(U1A-AUX_CL-Pad7)") (class "Default")
      (node (ref "U1") (pin "7") (pinfunction "AUX_CL_7") (pintype "input+no_connect"))
    )
    (net (code "63") (name "unconnected-(U1A-AUX_DA-Pad21)") (class "Default")
      (node (ref "U1") (pin "21") (pinfunction "AUX_DA_21") (pintype "passive+no_connect"))
    )
  )
)
